# miner.net
KiCad netlist of a schematic drawn in EAGLE
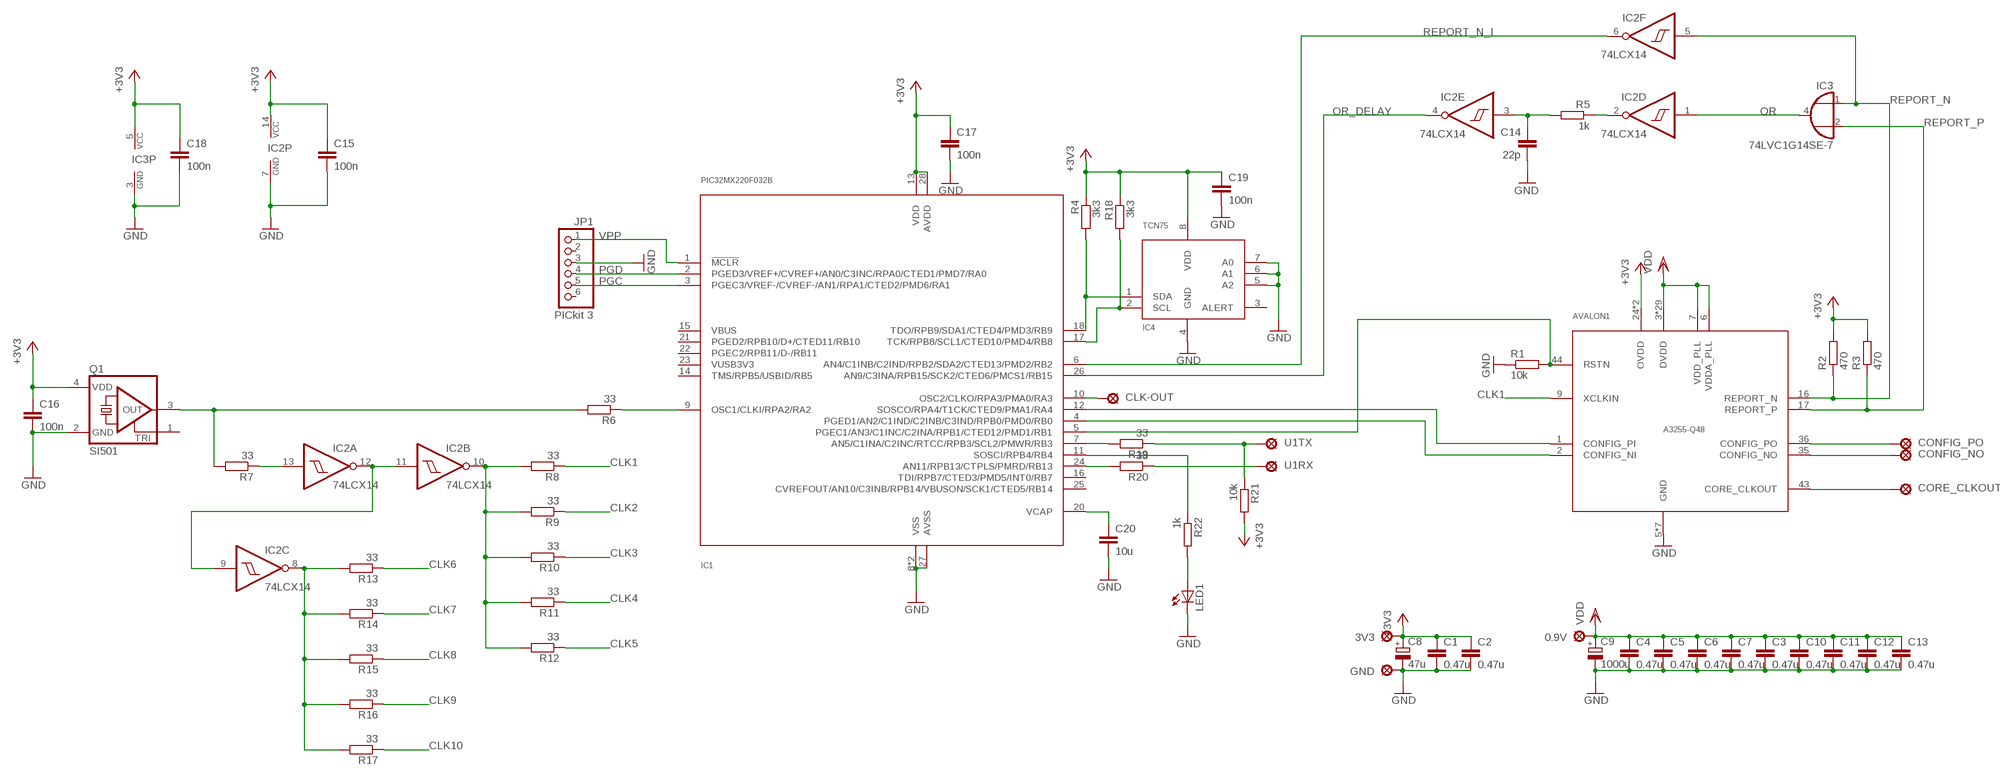
[diagram p0: schematic, sheet 1]

(export (version "E")
  (design (tool "Eeschema 10.0.6"))
  (components
    (comp (ref "0.9V")
      (value "LSP10")
      (footprint "eagle-import:LSP10")
      (libsource (lib "eagle-import") (part "LSP10"))
    )
    (comp (ref "3V3")
      (value "LSP10")
      (footprint "eagle-import:LSP10")
      (libsource (lib "eagle-import") (part "LSP10"))
    )
    (comp (ref "AVALON1")
      (value "A3255-Q48")
      (footprint "eagle-import:QFN48")
      (libsource (lib "eagle-import") (part "A3255-Q48"))
    )
    (comp (ref "C1")
      (value "0.47u")
      (footprint "eagle-import:C0805")
      (libsource (lib "eagle-import") (part "C-EUC0805"))
    )
    (comp (ref "C2")
      (value "0.47u")
      (footprint "eagle-import:C0805")
      (libsource (lib "eagle-import") (part "C-EUC0805"))
    )
    (comp (ref "C3")
      (value "0.47u")
      (footprint "eagle-import:C0805")
      (libsource (lib "eagle-import") (part "C-EUC0805"))
    )
    (comp (ref "C4")
      (value "0.47u")
      (footprint "eagle-import:C0805")
      (libsource (lib "eagle-import") (part "C-EUC0805"))
    )
    (comp (ref "C5")
      (value "0.47u")
      (footprint "eagle-import:C0805")
      (libsource (lib "eagle-import") (part "C-EUC0805"))
    )
    (comp (ref "C6")
      (value "0.47u")
      (footprint "eagle-import:C0805")
      (libsource (lib "eagle-import") (part "C-EUC0805"))
    )
    (comp (ref "C7")
      (value "0.47u")
      (footprint "eagle-import:C0805")
      (libsource (lib "eagle-import") (part "C-EUC0805"))
    )
    (comp (ref "C8")
      (value "47u")
      (footprint "eagle-import:150CLZ-1010")
      (libsource (lib "eagle-import") (part "CPOL-EU150CLZ-1010"))
    )
    (comp (ref "C9")
      (value "1000u")
      (footprint "eagle-import:150CLZ-1010")
      (libsource (lib "eagle-import") (part "CPOL-EU150CLZ-1010"))
    )
    (comp (ref "C10")
      (value "0.47u")
      (footprint "eagle-import:C0805")
      (libsource (lib "eagle-import") (part "C-EUC0805"))
    )
    (comp (ref "C11")
      (value "0.47u")
      (footprint "eagle-import:C0805")
      (libsource (lib "eagle-import") (part "C-EUC0805"))
    )
    (comp (ref "C12")
      (value "0.47u")
      (footprint "eagle-import:C0805")
      (libsource (lib "eagle-import") (part "C-EUC0805"))
    )
    (comp (ref "C13")
      (value "0.47u")
      (footprint "eagle-import:C0805")
      (libsource (lib "eagle-import") (part "C-EUC0805"))
    )
    (comp (ref "C14")
      (value "22p")
      (footprint "eagle-import:C0805")
      (libsource (lib "eagle-import") (part "C-EUC0805"))
    )
    (comp (ref "C15")
      (value "100n")
      (footprint "eagle-import:C0805")
      (libsource (lib "eagle-import") (part "C-EUC0805"))
    )
    (comp (ref "C16")
      (value "100n")
      (footprint "eagle-import:C0805")
      (libsource (lib "eagle-import") (part "C-EUC0805"))
    )
    (comp (ref "C17")
      (value "100n")
      (footprint "eagle-import:C0805")
      (libsource (lib "eagle-import") (part "C-EUC0805"))
    )
    (comp (ref "C18")
      (value "100n")
      (footprint "eagle-import:C0805")
      (libsource (lib "eagle-import") (part "C-EUC0805"))
    )
    (comp (ref "C19")
      (value "100n")
      (footprint "eagle-import:C0805")
      (libsource (lib "eagle-import") (part "C-EUC0805"))
    )
    (comp (ref "C20")
      (value "10u")
      (footprint "eagle-import:C0805")
      (libsource (lib "eagle-import") (part "C-EUC0805"))
    )
    (comp (ref "CLK-OUT")
      (value "LSP10")
      (footprint "eagle-import:LSP10")
      (libsource (lib "eagle-import") (part "LSP10"))
    )
    (comp (ref "CONFIG_NO")
      (value "LSP10")
      (footprint "eagle-import:LSP10")
      (libsource (lib "eagle-import") (part "LSP10"))
    )
    (comp (ref "CONFIG_PO")
      (value "LSP10")
      (footprint "eagle-import:LSP10")
      (libsource (lib "eagle-import") (part "LSP10"))
    )
    (comp (ref "CORE_CLKOUT")
      (value "LSP10")
      (footprint "eagle-import:LSP10")
      (libsource (lib "eagle-import") (part "LSP10"))
    )
    (comp (ref "GND")
      (value "LSP10")
      (footprint "eagle-import:LSP10")
      (libsource (lib "eagle-import") (part "LSP10"))
    )
    (comp (ref "IC1")
      (value "PIC32MX220F032B")
      (footprint "eagle-import:SSOP28")
      (libsource (lib "eagle-import") (part "PIC32MX220F032B"))
    )
    (comp (ref "IC2")
      (value "74LCX14")
      (footprint "eagle-import:SO14")
      (libsource (lib "eagle-import") (part "7414DLS"))
    )
    (comp (ref "IC3")
      (value "74LVC1G14SE-7")
      (footprint "eagle-import:SC70-5")
      (libsource (lib "eagle-import") (part "741G32DCKAHC"))
    )
    (comp (ref "IC4")
      (value "TCN75")
      (footprint "eagle-import:SOIC8")
      (libsource (lib "eagle-import") (part "TCN75"))
    )
    (comp (ref "JP1")
      (value "PICkit 3")
      (footprint "eagle-import:1X06")
      (libsource (lib "eagle-import") (part "PINHD-1X6"))
    )
    (comp (ref "LED1")
      (value "LED5MM")
      (footprint "eagle-import:LED5MM")
      (libsource (lib "eagle-import") (part "LED5MM"))
    )
    (comp (ref "Q1")
      (value "SI501")
      (footprint "eagle-import:DFN4")
      (libsource (lib "eagle-import") (part "SI501"))
    )
    (comp (ref "R1")
      (value "10k")
      (footprint "eagle-import:R0805")
      (libsource (lib "eagle-import") (part "R-EU_R0805"))
    )
    (comp (ref "R2")
      (value "470")
      (footprint "eagle-import:R0805")
      (libsource (lib "eagle-import") (part "R-EU_R0805"))
    )
    (comp (ref "R3")
      (value "470")
      (footprint "eagle-import:R0805")
      (libsource (lib "eagle-import") (part "R-EU_R0805"))
    )
    (comp (ref "R4")
      (value "3k3")
      (footprint "eagle-import:R0805")
      (libsource (lib "eagle-import") (part "R-EU_R0805"))
    )
    (comp (ref "R5")
      (value "1k")
      (footprint "eagle-import:R0805")
      (libsource (lib "eagle-import") (part "R-EU_R0805"))
    )
    (comp (ref "R6")
      (value "33")
      (footprint "eagle-import:R0805")
      (libsource (lib "eagle-import") (part "R-EU_R0805"))
    )
    (comp (ref "R7")
      (value "33")
      (footprint "eagle-import:R0805")
      (libsource (lib "eagle-import") (part "R-EU_R0805"))
    )
    (comp (ref "R8")
      (value "33")
      (footprint "eagle-import:R0805")
      (libsource (lib "eagle-import") (part "R-EU_R0805"))
    )
    (comp (ref "R9")
      (value "33")
      (footprint "eagle-import:R0805")
      (libsource (lib "eagle-import") (part "R-EU_R0805"))
    )
    (comp (ref "R10")
      (value "33")
      (footprint "eagle-import:R0805")
      (libsource (lib "eagle-import") (part "R-EU_R0805"))
    )
    (comp (ref "R11")
      (value "33")
      (footprint "eagle-import:R0805")
      (libsource (lib "eagle-import") (part "R-EU_R0805"))
    )
    (comp (ref "R12")
      (value "33")
      (footprint "eagle-import:R0805")
      (libsource (lib "eagle-import") (part "R-EU_R0805"))
    )
    (comp (ref "R13")
      (value "33")
      (footprint "eagle-import:R0805")
      (libsource (lib "eagle-import") (part "R-EU_R0805"))
    )
    (comp (ref "R14")
      (value "33")
      (footprint "eagle-import:R0805")
      (libsource (lib "eagle-import") (part "R-EU_R0805"))
    )
    (comp (ref "R15")
      (value "33")
      (footprint "eagle-import:R0805")
      (libsource (lib "eagle-import") (part "R-EU_R0805"))
    )
    (comp (ref "R16")
      (value "33")
      (footprint "eagle-import:R0805")
      (libsource (lib "eagle-import") (part "R-EU_R0805"))
    )
    (comp (ref "R17")
      (value "33")
      (footprint "eagle-import:R0805")
      (libsource (lib "eagle-import") (part "R-EU_R0805"))
    )
    (comp (ref "R18")
      (value "3k3")
      (footprint "eagle-import:R0805")
      (libsource (lib "eagle-import") (part "R-EU_R0805"))
    )
    (comp (ref "R19")
      (value "33")
      (footprint "eagle-import:R0805")
      (libsource (lib "eagle-import") (part "R-EU_R0805"))
    )
    (comp (ref "R20")
      (value "33")
      (footprint "eagle-import:R0805")
      (libsource (lib "eagle-import") (part "R-EU_R0805"))
    )
    (comp (ref "R21")
      (value "10k")
      (footprint "eagle-import:R0805")
      (libsource (lib "eagle-import") (part "R-EU_R0805"))
    )
    (comp (ref "R22")
      (value "1k")
      (footprint "eagle-import:R0805")
      (libsource (lib "eagle-import") (part "R-EU_R0805"))
    )
    (comp (ref "U1RX")
      (value "LSP10")
      (footprint "eagle-import:LSP10")
      (libsource (lib "eagle-import") (part "LSP10"))
    )
    (comp (ref "U1TX")
      (value "LSP10")
      (footprint "eagle-import:LSP10")
      (libsource (lib "eagle-import") (part "LSP10"))
    )
  )
  (nets
    (net (code "1") (name "+3V3") (class "Default")
      (node (ref "3V3") (pin "MP") (pinfunction "MP_MP") (pintype "passive"))
      (node (ref "AVALON1") (pin "24") (pinfunction "OVDD_24") (pintype "bidirectional"))
      (node (ref "AVALON1") (pin "37") (pinfunction "OVDD_37") (pintype "bidirectional"))
      (node (ref "C1") (pin "1") (pinfunction "1_1") (pintype "passive"))
      (node (ref "C15") (pin "1") (pinfunction "1_1") (pintype "passive"))
      (node (ref "C16") (pin "1") (pinfunction "1_1") (pintype "passive"))
      (node (ref "C17") (pin "1") (pinfunction "1_1") (pintype "passive"))
      (node (ref "C18") (pin "1") (pinfunction "1_1") (pintype "passive"))
      (node (ref "C19") (pin "1") (pinfunction "1_1") (pintype "passive"))
      (node (ref "C2") (pin "1") (pinfunction "1_1") (pintype "passive"))
      (node (ref "C8") (pin "+") (pinfunction "+_+") (pintype "passive"))
      (node (ref "IC1") (pin "13") (pinfunction "VDD_13") (pintype "bidirectional"))
      (node (ref "IC1") (pin "28") (pinfunction "AVDD_28") (pintype "bidirectional"))
      (node (ref "IC2") (pin "14") (pinfunction "VCC_14") (pintype "power_in"))
      (node (ref "IC3") (pin "5") (pinfunction "VCC_5") (pintype "power_in"))
      (node (ref "IC4") (pin "8") (pinfunction "VDD_8") (pintype "bidirectional"))
      (node (ref "Q1") (pin "4") (pinfunction "VDD_4") (pintype "power_in"))
      (node (ref "R18") (pin "1") (pinfunction "1_1") (pintype "passive"))
      (node (ref "R2") (pin "2") (pinfunction "2_2") (pintype "passive"))
      (node (ref "R21") (pin "2") (pinfunction "2_2") (pintype "passive"))
      (node (ref "R3") (pin "2") (pinfunction "2_2") (pintype "passive"))
      (node (ref "R4") (pin "1") (pinfunction "1_1") (pintype "passive"))
    )
    (net (code "2") (name "/CLK1") (class "Default")
      (node (ref "AVALON1") (pin "9") (pinfunction "XCLKIN_9") (pintype "bidirectional"))
      (node (ref "R8") (pin "1") (pinfunction "1_1") (pintype "passive"))
    )
    (net (code "3") (name "/CLK2") (class "Default")
      (node (ref "R9") (pin "1") (pinfunction "1_1") (pintype "passive"))
    )
    (net (code "4") (name "/CLK3") (class "Default")
      (node (ref "R10") (pin "1") (pinfunction "1_1") (pintype "passive"))
    )
    (net (code "5") (name "/CLK4") (class "Default")
      (node (ref "R11") (pin "1") (pinfunction "1_1") (pintype "passive"))
    )
    (net (code "6") (name "/CLK5") (class "Default")
      (node (ref "R12") (pin "1") (pinfunction "1_1") (pintype "passive"))
    )
    (net (code "7") (name "/CLK6") (class "Default")
      (node (ref "R13") (pin "1") (pinfunction "1_1") (pintype "passive"))
    )
    (net (code "8") (name "/CLK7") (class "Default")
      (node (ref "R14") (pin "1") (pinfunction "1_1") (pintype "passive"))
    )
    (net (code "9") (name "/CLK8") (class "Default")
      (node (ref "R15") (pin "1") (pinfunction "1_1") (pintype "passive"))
    )
    (net (code "10") (name "/CLK9") (class "Default")
      (node (ref "R16") (pin "1") (pinfunction "1_1") (pintype "passive"))
    )
    (net (code "11") (name "/CLK10") (class "Default")
      (node (ref "R17") (pin "1") (pinfunction "1_1") (pintype "passive"))
    )
    (net (code "12") (name "/OR") (class "Default")
      (node (ref "IC2") (pin "1") (pinfunction "I_1") (pintype "input"))
      (node (ref "IC3") (pin "4") (pinfunction "O_4") (pintype "output"))
    )
    (net (code "13") (name "/OR_DELAY") (class "Default")
      (node (ref "IC1") (pin "26") (pinfunction "AN9/C3INA/RPB15/SCK2/CTED6/PMCS1/RB15_26") (pintype "bidirectional"))
      (node (ref "IC2") (pin "4") (pinfunction "O_4") (pintype "output"))
    )
    (net (code "14") (name "/PGC") (class "Default")
      (node (ref "IC1") (pin "3") (pinfunction "PGEC3/VREF-/CVREF-/AN1/RPA1/CTED2/PMD6/RA1_3") (pintype "bidirectional"))
      (node (ref "JP1") (pin "5") (pinfunction "5_5") (pintype "passive"))
    )
    (net (code "15") (name "/PGD") (class "Default")
      (node (ref "IC1") (pin "2") (pinfunction "PGED3/VREF+/CVREF+/AN0/C3INC/RPA0/CTED1/PMD7/RA0_2") (pintype "bidirectional"))
      (node (ref "JP1") (pin "4") (pinfunction "4_4") (pintype "passive"))
    )
    (net (code "16") (name "/REPORT_N") (class "Default")
      (node (ref "AVALON1") (pin "16") (pinfunction "REPORT_N_16") (pintype "bidirectional"))
      (node (ref "IC2") (pin "5") (pinfunction "I_5") (pintype "input"))
      (node (ref "IC3") (pin "1") (pinfunction "I0_1") (pintype "input"))
      (node (ref "R2") (pin "1") (pinfunction "1_1") (pintype "passive"))
    )
    (net (code "17") (name "/REPORT_N_I") (class "Default")
      (node (ref "IC1") (pin "6") (pinfunction "AN4/C1INB/C2IND/RPB2/SDA2/CTED13/PMD2/RB2_6") (pintype "bidirectional"))
      (node (ref "IC2") (pin "6") (pinfunction "O_6") (pintype "output"))
    )
    (net (code "18") (name "/REPORT_P") (class "Default")
      (node (ref "AVALON1") (pin "17") (pinfunction "REPORT_P_17") (pintype "bidirectional"))
      (node (ref "IC3") (pin "2") (pinfunction "I1_2") (pintype "input"))
      (node (ref "R3") (pin "1") (pinfunction "1_1") (pintype "passive"))
    )
    (net (code "19") (name "/VPP") (class "Default")
      (node (ref "IC1") (pin "1") (pinfunction "~{MCLR}_1") (pintype "bidirectional"))
      (node (ref "JP1") (pin "1") (pinfunction "1_1") (pintype "passive"))
    )
    (net (code "20") (name "GND") (class "Default")
      (node (ref "AVALON1") (pin "12") (pinfunction "GND_12") (pintype "bidirectional"))
      (node (ref "AVALON1") (pin "23") (pinfunction "GND_23") (pintype "bidirectional"))
      (node (ref "AVALON1") (pin "27") (pinfunction "GND_27") (pintype "bidirectional"))
      (node (ref "AVALON1") (pin "38") (pinfunction "GND_38") (pintype "bidirectional"))
      (node (ref "AVALON1") (pin "5") (pinfunction "GND_5") (pintype "bidirectional"))
      (node (ref "AVALON1") (pin "8") (pinfunction "GND_8") (pintype "bidirectional"))
      (node (ref "AVALON1") (pin "EP-PAD") (pinfunction "GND_EP-PAD") (pintype "bidirectional"))
      (node (ref "C1") (pin "2") (pinfunction "2_2") (pintype "passive"))
      (node (ref "C10") (pin "2") (pinfunction "2_2") (pintype "passive"))
      (node (ref "C11") (pin "2") (pinfunction "2_2") (pintype "passive"))
      (node (ref "C12") (pin "2") (pinfunction "2_2") (pintype "passive"))
      (node (ref "C13") (pin "2") (pinfunction "2_2") (pintype "passive"))
      (node (ref "C14") (pin "2") (pinfunction "2_2") (pintype "passive"))
      (node (ref "C15") (pin "2") (pinfunction "2_2") (pintype "passive"))
      (node (ref "C16") (pin "2") (pinfunction "2_2") (pintype "passive"))
      (node (ref "C17") (pin "2") (pinfunction "2_2") (pintype "passive"))
      (node (ref "C18") (pin "2") (pinfunction "2_2") (pintype "passive"))
      (node (ref "C19") (pin "2") (pinfunction "2_2") (pintype "passive"))
      (node (ref "C2") (pin "2") (pinfunction "2_2") (pintype "passive"))
      (node (ref "C20") (pin "2") (pinfunction "2_2") (pintype "passive"))
      (node (ref "C3") (pin "2") (pinfunction "2_2") (pintype "passive"))
      (node (ref "C4") (pin "2") (pinfunction "2_2") (pintype "passive"))
      (node (ref "C5") (pin "2") (pinfunction "2_2") (pintype "passive"))
      (node (ref "C6") (pin "2") (pinfunction "2_2") (pintype "passive"))
      (node (ref "C7") (pin "2") (pinfunction "2_2") (pintype "passive"))
      (node (ref "C8") (pin "-") (pinfunction "-_-") (pintype "passive"))
      (node (ref "C9") (pin "-") (pinfunction "-_-") (pintype "passive"))
      (node (ref "GND") (pin "MP") (pinfunction "MP_MP") (pintype "passive"))
      (node (ref "IC1") (pin "19") (pinfunction "VSS_19") (pintype "bidirectional"))
      (node (ref "IC1") (pin "27") (pinfunction "AVSS_27") (pintype "bidirectional"))
      (node (ref "IC1") (pin "8") (pinfunction "VSS_8") (pintype "bidirectional"))
      (node (ref "IC2") (pin "7") (pinfunction "GND_7") (pintype "power_in"))
      (node (ref "IC3") (pin "3") (pinfunction "GND_3") (pintype "power_in"))
      (node (ref "IC4") (pin "4") (pinfunction "GND_4") (pintype "bidirectional"))
      (node (ref "IC4") (pin "5") (pinfunction "A2_5") (pintype "bidirectional"))
      (node (ref "IC4") (pin "6") (pinfunction "A1_6") (pintype "bidirectional"))
      (node (ref "IC4") (pin "7") (pinfunction "A0_7") (pintype "bidirectional"))
      (node (ref "JP1") (pin "3") (pinfunction "3_3") (pintype "passive"))
      (node (ref "LED1") (pin "K") (pinfunction "C_K") (pintype "passive"))
      (node (ref "Q1") (pin "2") (pinfunction "GND_2") (pintype "power_in"))
      (node (ref "R1") (pin "1") (pinfunction "1_1") (pintype "passive"))
    )
    (net (code "21") (name "Net-(AVALON1-CONFIG_NI)") (class "Default")
      (node (ref "AVALON1") (pin "2") (pinfunction "CONFIG_NI_2") (pintype "bidirectional"))
      (node (ref "IC1") (pin "4") (pinfunction "PGED1/AN2/C1IND/C2INB/C3IND/RPB0/PMD0/RB0_4") (pintype "bidirectional"))
    )
    (net (code "22") (name "Net-(AVALON1-CONFIG_NO)") (class "Default")
      (node (ref "AVALON1") (pin "35") (pinfunction "CONFIG_NO_35") (pintype "bidirectional"))
      (node (ref "CONFIG_NO") (pin "MP") (pinfunction "MP_MP") (pintype "passive"))
    )
    (net (code "23") (name "Net-(AVALON1-CONFIG_PI)") (class "Default")
      (node (ref "AVALON1") (pin "1") (pinfunction "CONFIG_PI_1") (pintype "bidirectional"))
      (node (ref "IC1") (pin "12") (pinfunction "SOSCO/RPA4/T1CK/CTED9/PMA1/RA4_12") (pintype "bidirectional"))
    )
    (net (code "24") (name "Net-(AVALON1-CONFIG_PO)") (class "Default")
      (node (ref "AVALON1") (pin "36") (pinfunction "CONFIG_PO_36") (pintype "bidirectional"))
      (node (ref "CONFIG_PO") (pin "MP") (pinfunction "MP_MP") (pintype "passive"))
    )
    (net (code "25") (name "Net-(AVALON1-CORE_CLKOUT)") (class "Default")
      (node (ref "AVALON1") (pin "43") (pinfunction "CORE_CLKOUT_43") (pintype "bidirectional"))
      (node (ref "CORE_CLKOUT") (pin "MP") (pinfunction "MP_MP") (pintype "passive"))
    )
    (net (code "26") (name "Net-(AVALON1-RSTN)") (class "Default")
      (node (ref "AVALON1") (pin "44") (pinfunction "RSTN_44") (pintype "bidirectional"))
      (node (ref "IC1") (pin "5") (pinfunction "PGEC1/AN3/C1INC/C2INA/RPB1/CTED12/PMD1/RB1_5") (pintype "bidirectional"))
      (node (ref "R1") (pin "2") (pinfunction "2_2") (pintype "passive"))
    )
    (net (code "27") (name "Net-(IC1-AN5{slash}C1INA{slash}C2INC{slash}RTCC{slash}RPB3{slash}SCL2{slash}PMWR{slash}RB3)") (class "Default")
      (node (ref "IC1") (pin "7") (pinfunction "AN5/C1INA/C2INC/RTCC/RPB3/SCL2/PMWR/RB3_7") (pintype "bidirectional"))
      (node (ref "R19") (pin "2") (pinfunction "2_2") (pintype "passive"))
    )
    (net (code "28") (name "Net-(IC1-AN11{slash}RPB13{slash}CTPLS{slash}PMRD{slash}RB13)") (class "Default")
      (node (ref "IC1") (pin "24") (pinfunction "AN11/RPB13/CTPLS/PMRD/RB13_24") (pintype "bidirectional"))
      (node (ref "R20") (pin "2") (pinfunction "2_2") (pintype "passive"))
    )
    (net (code "29") (name "Net-(IC1-OSC1{slash}CLKI{slash}RPA2{slash}RA2)") (class "Default")
      (node (ref "IC1") (pin "9") (pinfunction "OSC1/CLKI/RPA2/RA2_9") (pintype "bidirectional"))
      (node (ref "R6") (pin "1") (pinfunction "1_1") (pintype "passive"))
    )
    (net (code "30") (name "Net-(IC1-OSC2{slash}CLKO{slash}RPA3{slash}PMA0{slash}RA3)") (class "Default")
      (node (ref "CLK-OUT") (pin "MP") (pinfunction "MP_MP") (pintype "passive"))
      (node (ref "IC1") (pin "10") (pinfunction "OSC2/CLKO/RPA3/PMA0/RA3_10") (pintype "bidirectional"))
    )
    (net (code "31") (name "Net-(IC1-SOSCI{slash}RPB4{slash}RB4)") (class "Default")
      (node (ref "IC1") (pin "11") (pinfunction "SOSCI/RPB4/RB4_11") (pintype "bidirectional"))
      (node (ref "R22") (pin "1") (pinfunction "1_1") (pintype "passive"))
    )
    (net (code "32") (name "Net-(IC1-TCK{slash}RPB8{slash}SCL1{slash}CTED10{slash}PMD4{slash}RB8)") (class "Default")
      (node (ref "IC1") (pin "17") (pinfunction "TCK/RPB8/SCL1/CTED10/PMD4/RB8_17") (pintype "bidirectional"))
      (node (ref "IC4") (pin "2") (pinfunction "SCL_2") (pintype "bidirectional"))
      (node (ref "R18") (pin "2") (pinfunction "2_2") (pintype "passive"))
    )
    (net (code "33") (name "Net-(IC1-TDO{slash}RPB9{slash}SDA1{slash}CTED4{slash}PMD3{slash}RB9)") (class "Default")
      (node (ref "IC1") (pin "18") (pinfunction "TDO/RPB9/SDA1/CTED4/PMD3/RB9_18") (pintype "bidirectional"))
      (node (ref "IC4") (pin "1") (pinfunction "SDA_1") (pintype "bidirectional"))
      (node (ref "R4") (pin "2") (pinfunction "2_2") (pintype "passive"))
    )
    (net (code "34") (name "Net-(IC1-VCAP)") (class "Default")
      (node (ref "C20") (pin "1") (pinfunction "1_1") (pintype "passive"))
      (node (ref "IC1") (pin "20") (pinfunction "VCAP_20") (pintype "bidirectional"))
    )
    (net (code "35") (name "Net-(IC2A-I)") (class "Default")
      (node (ref "IC2") (pin "13") (pinfunction "I_13") (pintype "input"))
      (node (ref "R7") (pin "1") (pinfunction "1_1") (pintype "passive"))
    )
    (net (code "36") (name "Net-(IC2A-O)") (class "Default")
      (node (ref "IC2") (pin "11") (pinfunction "I_11") (pintype "input"))
      (node (ref "IC2") (pin "12") (pinfunction "O_12") (pintype "output"))
      (node (ref "IC2") (pin "9") (pinfunction "I_9") (pintype "input"))
    )
    (net (code "37") (name "Net-(IC2B-O)") (class "Default")
      (node (ref "IC2") (pin "10") (pinfunction "O_10") (pintype "output"))
      (node (ref "R10") (pin "2") (pinfunction "2_2") (pintype "passive"))
      (node (ref "R11") (pin "2") (pinfunction "2_2") (pintype "passive"))
      (node (ref "R12") (pin "2") (pinfunction "2_2") (pintype "passive"))
      (node (ref "R8") (pin "2") (pinfunction "2_2") (pintype "passive"))
      (node (ref "R9") (pin "2") (pinfunction "2_2") (pintype "passive"))
    )
    (net (code "38") (name "Net-(IC2C-O)") (class "Default")
      (node (ref "IC2") (pin "8") (pinfunction "O_8") (pintype "output"))
      (node (ref "R13") (pin "2") (pinfunction "2_2") (pintype "passive"))
      (node (ref "R14") (pin "2") (pinfunction "2_2") (pintype "passive"))
      (node (ref "R15") (pin "2") (pinfunction "2_2") (pintype "passive"))
      (node (ref "R16") (pin "2") (pinfunction "2_2") (pintype "passive"))
      (node (ref "R17") (pin "2") (pinfunction "2_2") (pintype "passive"))
    )
    (net (code "39") (name "Net-(IC2D-O)") (class "Default")
      (node (ref "IC2") (pin "2") (pinfunction "O_2") (pintype "output"))
      (node (ref "R5") (pin "1") (pinfunction "1_1") (pintype "passive"))
    )
    (net (code "40") (name "Net-(IC2E-I)") (class "Default")
      (node (ref "C14") (pin "1") (pinfunction "1_1") (pintype "passive"))
      (node (ref "IC2") (pin "3") (pinfunction "I_3") (pintype "input"))
      (node (ref "R5") (pin "2") (pinfunction "2_2") (pintype "passive"))
    )
    (net (code "41") (name "Net-(LED1-PadA)") (class "Default")
      (node (ref "LED1") (pin "A") (pinfunction "A_A") (pintype "passive"))
      (node (ref "R22") (pin "2") (pinfunction "2_2") (pintype "passive"))
    )
    (net (code "42") (name "Net-(Q1-OUT)") (class "Default")
      (node (ref "Q1") (pin "3") (pinfunction "OUT_3") (pintype "output"))
      (node (ref "R6") (pin "2") (pinfunction "2_2") (pintype "passive"))
      (node (ref "R7") (pin "2") (pinfunction "2_2") (pintype "passive"))
    )
    (net (code "43") (name "Net-(R19-Pad1)") (class "Default")
      (node (ref "R19") (pin "1") (pinfunction "1_1") (pintype "passive"))
      (node (ref "R21") (pin "1") (pinfunction "1_1") (pintype "passive"))
      (node (ref "U1TX") (pin "MP") (pinfunction "MP_MP") (pintype "passive"))
    )
    (net (code "44") (name "Net-(R20-Pad1)") (class "Default")
      (node (ref "R20") (pin "1") (pinfunction "1_1") (pintype "passive"))
      (node (ref "U1RX") (pin "MP") (pinfunction "MP_MP") (pintype "passive"))
    )
    (net (code "45") (name "VDD") (class "Default")
      (node (ref "0.9V") (pin "MP") (pinfunction "MP_MP") (pintype "passive"))
      (node (ref "AVALON1") (pin "10") (pinfunction "DVDD_10") (pintype "bidirectional"))
      (node (ref "AVALON1") (pin "11") (pinfunction "DVDD_11") (pintype "bidirectional"))
      (node (ref "AVALON1") (pin "13") (pinfunction "DVDD_13") (pintype "bidirectional"))
      (node (ref "AVALON1") (pin "14") (pinfunction "DVDD_14") (pintype "bidirectional"))
      (node (ref "AVALON1") (pin "15") (pinfunction "DVDD_15") (pintype "bidirectional"))
      (node (ref "AVALON1") (pin "18") (pinfunction "DVDD_18") (pintype "bidirectional"))
      (node (ref "AVALON1") (pin "19") (pinfunction "DVDD_19") (pintype "bidirectional"))
      (node (ref "AVALON1") (pin "20") (pinfunction "DVDD_20") (pintype "bidirectional"))
      (node (ref "AVALON1") (pin "21") (pinfunction "DVDD_21") (pintype "bidirectional"))
      (node (ref "AVALON1") (pin "22") (pinfunction "DVDD_22") (pintype "bidirectional"))
      (node (ref "AVALON1") (pin "25") (pinfunction "DVDD_25") (pintype "bidirectional"))
      (node (ref "AVALON1") (pin "26") (pinfunction "DVDD_26") (pintype "bidirectional"))
      (node (ref "AVALON1") (pin "28") (pinfunction "DVDD_28") (pintype "bidirectional"))
      (node (ref "AVALON1") (pin "29") (pinfunction "DVDD_29") (pintype "bidirectional"))
      (node (ref "AVALON1") (pin "3") (pinfunction "DVDD_3") (pintype "bidirectional"))
      (node (ref "AVALON1") (pin "30") (pinfunction "DVDD_30") (pintype "bidirectional"))
      (node (ref "AVALON1") (pin "31") (pinfunction "DVDD_31") (pintype "bidirectional"))
      (node (ref "AVALON1") (pin "32") (pinfunction "DVDD_32") (pintype "bidirectional"))
      (node (ref "AVALON1") (pin "33") (pinfunction "DVDD_33") (pintype "bidirectional"))
      (node (ref "AVALON1") (pin "34") (pinfunction "DVDD_34") (pintype "bidirectional"))
      (node (ref "AVALON1") (pin "39") (pinfunction "DVDD_39") (pintype "bidirectional"))
      (node (ref "AVALON1") (pin "4") (pinfunction "DVDD_4") (pintype "bidirectional"))
      (node (ref "AVALON1") (pin "40") (pinfunction "DVDD_40") (pintype "bidirectional"))
      (node (ref "AVALON1") (pin "41") (pinfunction "DVDD_41") (pintype "bidirectional"))
      (node (ref "AVALON1") (pin "42") (pinfunction "DVDD_42") (pintype "bidirectional"))
      (node (ref "AVALON1") (pin "45") (pinfunction "DVDD_45") (pintype "bidirectional"))
      (node (ref "AVALON1") (pin "46") (pinfunction "DVDD_46") (pintype "bidirectional"))
      (node (ref "AVALON1") (pin "47") (pinfunction "DVDD_47") (pintype "bidirectional"))
      (node (ref "AVALON1") (pin "48") (pinfunction "DVDD_48") (pintype "bidirectional"))
      (node (ref "AVALON1") (pin "6") (pinfunction "VDDA_PLL_6") (pintype "bidirectional"))
      (node (ref "AVALON1") (pin "7") (pinfunction "VDD_PLL_7") (pintype "bidirectional"))
      (node (ref "C10") (pin "1") (pinfunction "1_1") (pintype "passive"))
      (node (ref "C11") (pin "1") (pinfunction "1_1") (pintype "passive"))
      (node (ref "C12") (pin "1") (pinfunction "1_1") (pintype "passive"))
      (node (ref "C13") (pin "1") (pinfunction "1_1") (pintype "passive"))
      (node (ref "C3") (pin "1") (pinfunction "1_1") (pintype "passive"))
      (node (ref "C4") (pin "1") (pinfunction "1_1") (pintype "passive"))
      (node (ref "C5") (pin "1") (pinfunction "1_1") (pintype "passive"))
      (node (ref "C6") (pin "1") (pinfunction "1_1") (pintype "passive"))
      (node (ref "C7") (pin "1") (pinfunction "1_1") (pintype "passive"))
      (node (ref "C9") (pin "+") (pinfunction "+_+") (pintype "passive"))
    )
    (net (code "46") (name "unconnected-(IC1-CVREFOUT{slash}AN10{slash}C3INB{slash}RPB14{slash}VBUSON{slash}SCK1{slash}CTED5{slash}RB14-Pad25)") (class "Default")
      (node (ref "IC1") (pin "25") (pinfunction "CVREFOUT/AN10/C3INB/RPB14/VBUSON/SCK1/CTED5/RB14_25") (pintype "bidirectional"))
    )
    (net (code "47") (name "unconnected-(IC1-PGEC2{slash}RPB11{slash}D-{slash}RB11-Pad22)") (class "Default")
      (node (ref "IC1") (pin "22") (pinfunction "PGEC2/RPB11/D-/RB11_22") (pintype "bidirectional"))
    )
    (net (code "48") (name "unconnected-(IC1-PGED2{slash}RPB10{slash}D+{slash}CTED11{slash}RB10-Pad21)") (class "Default")
      (node (ref "IC1") (pin "21") (pinfunction "PGED2/RPB10/D+/CTED11/RB10_21") (pintype "bidirectional"))
    )
    (net (code "49") (name "unconnected-(IC1-TDI{slash}RPB7{slash}CTED3{slash}PMD5{slash}INT0{slash}RB7-Pad16)") (class "Default")
      (node (ref "IC1") (pin "16") (pinfunction "TDI/RPB7/CTED3/PMD5/INT0/RB7_16") (pintype "bidirectional"))
    )
    (net (code "50") (name "unconnected-(IC1-TMS{slash}RPB5{slash}USBID{slash}RB5-Pad14)") (class "Default")
      (node (ref "IC1") (pin "14") (pinfunction "TMS/RPB5/USBID/RB5_14") (pintype "bidirectional"))
    )
    (net (code "51") (name "unconnected-(IC1-VBUS-Pad15)") (class "Default")
      (node (ref "IC1") (pin "15") (pinfunction "VBUS_15") (pintype "bidirectional"))
    )
    (net (code "52") (name "unconnected-(IC1-VUSB3V3-Pad23)") (class "Default")
      (node (ref "IC1") (pin "23") (pinfunction "VUSB3V3_23") (pintype "bidirectional"))
    )
    (net (code "53") (name "unconnected-(IC4-ALERT-Pad3)") (class "Default")
      (node (ref "IC4") (pin "3") (pinfunction "ALERT_3") (pintype "bidirectional"))
    )
    (net (code "54") (name "unconnected-(JP1-Pad2)") (class "Default")
      (node (ref "JP1") (pin "2") (pinfunction "2_2") (pintype "passive"))
    )
    (net (code "55") (name "unconnected-(JP1-Pad6)") (class "Default")
      (node (ref "JP1") (pin "6") (pinfunction "6_6") (pintype "passive"))
    )
    (net (code "56") (name "unconnected-(Q1-TRI-Pad1)") (class "Default")
      (node (ref "Q1") (pin "1") (pinfunction "TRI_1") (pintype "input"))
    )
  )
)
